# MurataBreakout_rev2.net
KiCad netlist of a schematic drawn in EAGLE
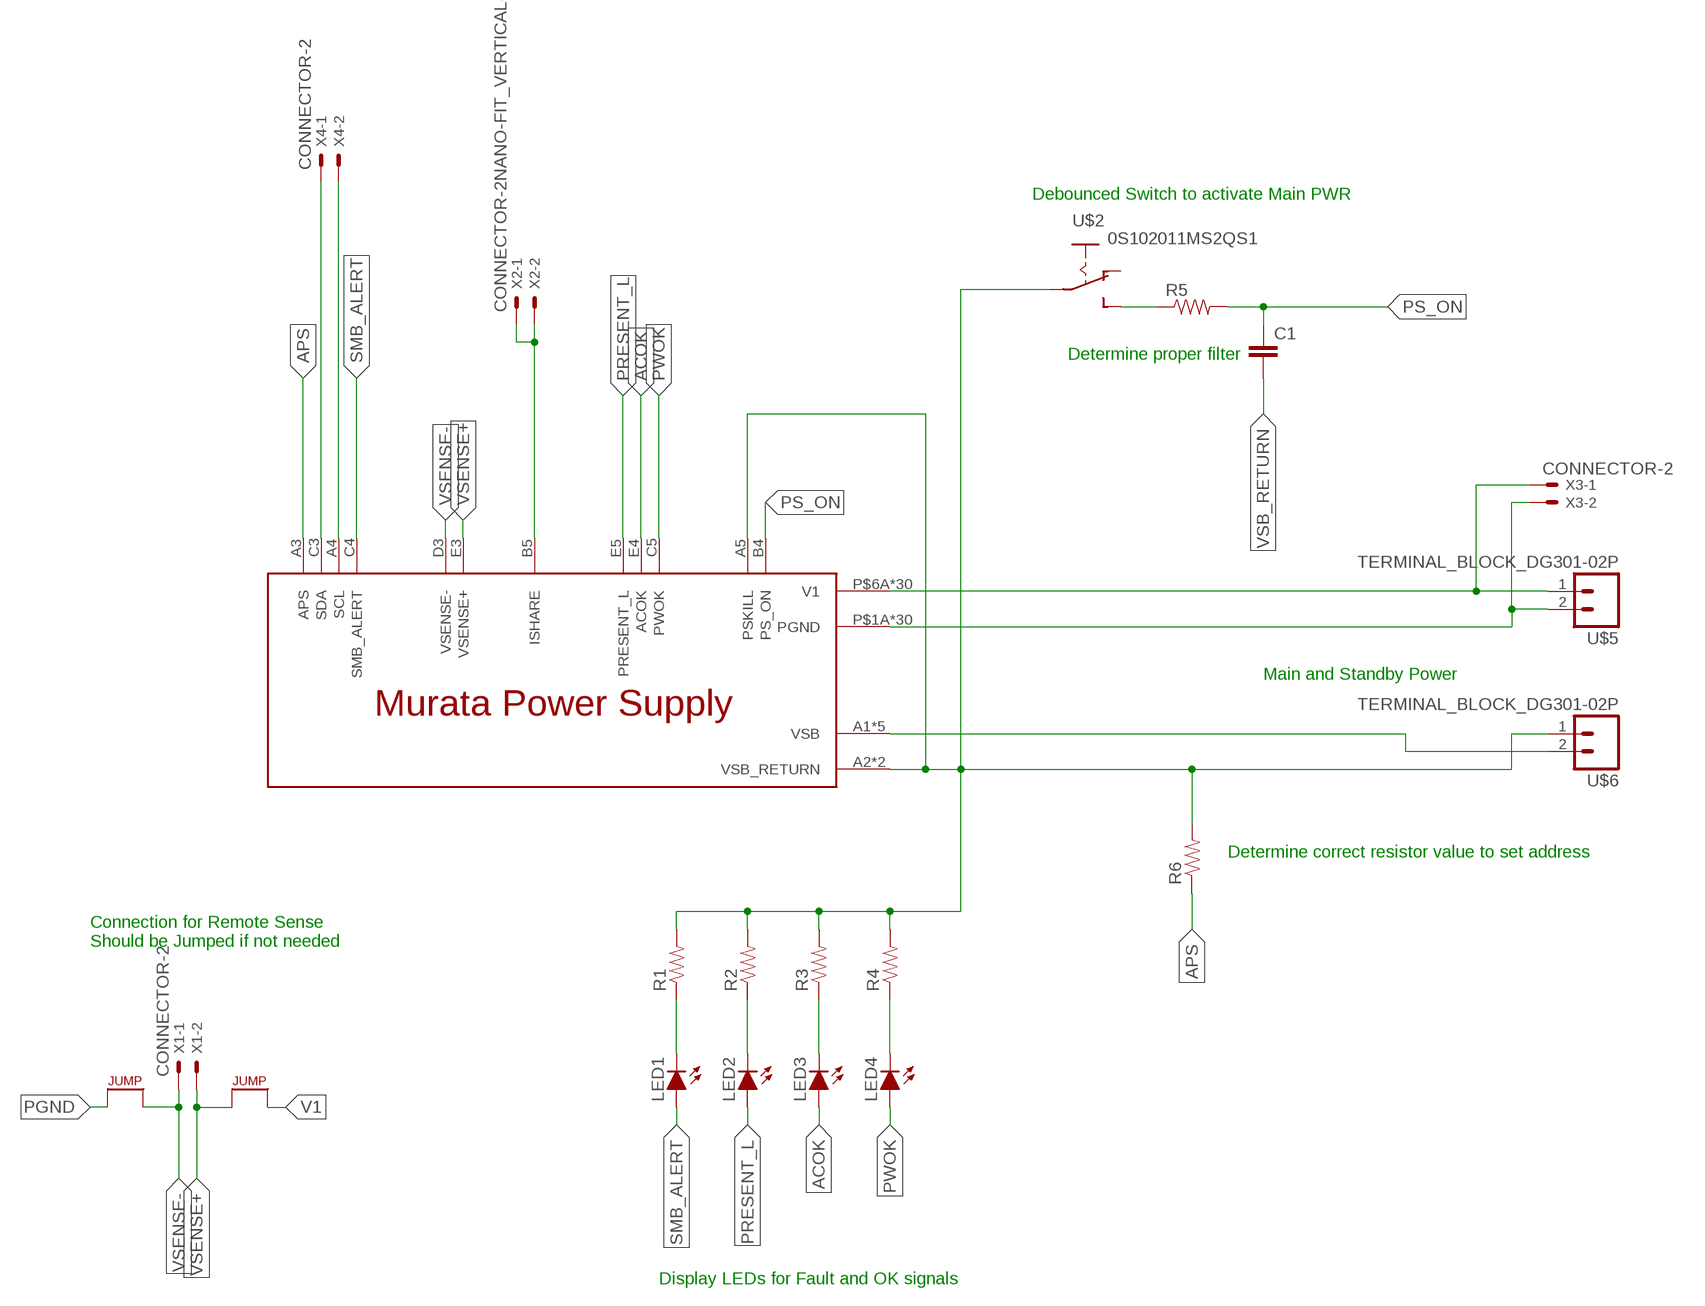
[diagram p0: schematic, sheet 1]

(export (version "E")
  (design (tool "Eeschema 10.0.6"))
  (components
    (comp (ref "C1")
      (value "CAP0805")
      (footprint "eagle-import:0805")
      (libsource (lib "eagle-import") (part "CAP0805"))
    )
    (comp (ref "LED1")
      (value "LED-0805")
      (footprint "eagle-import:LED-805")
      (libsource (lib "eagle-import") (part "LED-0805"))
    )
    (comp (ref "LED2")
      (value "LED-0805")
      (footprint "eagle-import:LED-805")
      (libsource (lib "eagle-import") (part "LED-0805"))
    )
    (comp (ref "LED3")
      (value "LED-0805")
      (footprint "eagle-import:LED-805")
      (libsource (lib "eagle-import") (part "LED-0805"))
    )
    (comp (ref "LED4")
      (value "LED-0805")
      (footprint "eagle-import:LED-805")
      (libsource (lib "eagle-import") (part "LED-0805"))
    )
    (comp (ref "R1")
      (value "RESISTOR0805-RES")
      (footprint "eagle-import:0805")
      (libsource (lib "eagle-import") (part "RESISTOR0805-RES"))
    )
    (comp (ref "R2")
      (value "RESISTOR0805-RES")
      (footprint "eagle-import:0805")
      (libsource (lib "eagle-import") (part "RESISTOR0805-RES"))
    )
    (comp (ref "R3")
      (value "RESISTOR0805-RES")
      (footprint "eagle-import:0805")
      (libsource (lib "eagle-import") (part "RESISTOR0805-RES"))
    )
    (comp (ref "R4")
      (value "RESISTOR0805-RES")
      (footprint "eagle-import:0805")
      (libsource (lib "eagle-import") (part "RESISTOR0805-RES"))
    )
    (comp (ref "R5")
      (value "RESISTOR0805-RES")
      (footprint "eagle-import:0805")
      (libsource (lib "eagle-import") (part "RESISTOR0805-RES"))
    )
    (comp (ref "R6")
      (value "RESISTOR0805-RES")
      (footprint "eagle-import:0805")
      (libsource (lib "eagle-import") (part "RESISTOR0805-RES"))
    )
    (comp (ref "U$1")
      (value "MURATA_POWER_SUPPLY")
      (footprint "eagle-import:MURATA_POWER_SUPPLY_CONNECTOR")
      (libsource (lib "eagle-import") (part "MURATA_POWER_SUPPLY"))
    )
    (comp (ref "U$2")
      (value "0S102011MS2QS1")
      (footprint "eagle-import:0S102011MS2QS1")
      (libsource (lib "eagle-import") (part "0S102011MS2QS1"))
    )
    (comp (ref "U$3")
      (value "JUMPER.1")
      (footprint "eagle-import:1X02")
      (libsource (lib "eagle-import") (part "JUMPER.1"))
    )
    (comp (ref "U$4")
      (value "JUMPER.1")
      (footprint "eagle-import:1X02")
      (libsource (lib "eagle-import") (part "JUMPER.1"))
    )
    (comp (ref "U$5")
      (value "TERMINAL_BLOCK_DG301-02P")
      (footprint "eagle-import:DG301-02P")
      (libsource (lib "eagle-import") (part "TERMINAL_BLOCK_DG301-02P"))
    )
    (comp (ref "U$6")
      (value "TERMINAL_BLOCK_DG301-02P")
      (footprint "eagle-import:DG301-02P")
      (libsource (lib "eagle-import") (part "TERMINAL_BLOCK_DG301-02P"))
    )
    (comp (ref "X1")
      (value "CONNECTOR-2")
      (footprint "eagle-import:MINIFIT_5566-2")
      (libsource (lib "eagle-import") (part "CONNECTOR-2"))
    )
    (comp (ref "X2")
      (value "CONNECTOR-2NANO-FIT_VERTICAL-2")
      (footprint "eagle-import:NANO-FIT_VERTICAL-2")
      (libsource (lib "eagle-import") (part "CONNECTOR-2NANO-FIT_VERTICAL-2"))
    )
    (comp (ref "X3")
      (value "CONNECTOR-2")
      (footprint "eagle-import:MINIFIT_5566-2")
      (libsource (lib "eagle-import") (part "CONNECTOR-2"))
    )
    (comp (ref "X4")
      (value "CONNECTOR-2")
      (footprint "eagle-import:MINIFIT_5566-2")
      (libsource (lib "eagle-import") (part "CONNECTOR-2"))
    )
  )
  (nets
    (net (code "1") (name "ACOK") (class "Default")
      (node (ref "LED3") (pin "A") (pinfunction "A_A") (pintype "passive"))
      (node (ref "U$1") (pin "E4") (pinfunction "ACOK_E4") (pintype "bidirectional"))
    )
    (net (code "2") (name "APS") (class "Default")
      (node (ref "R6") (pin "1") (pinfunction "1_1") (pintype "passive"))
      (node (ref "U$1") (pin "A3") (pinfunction "APS_A3") (pintype "bidirectional"))
    )
    (net (code "3") (name "Net-(LED1-PadC)") (class "Default")
      (node (ref "LED1") (pin "C") (pinfunction "C_C") (pintype "passive"))
      (node (ref "R1") (pin "1") (pinfunction "1_1") (pintype "passive"))
    )
    (net (code "4") (name "Net-(LED2-PadC)") (class "Default")
      (node (ref "LED2") (pin "C") (pinfunction "C_C") (pintype "passive"))
      (node (ref "R2") (pin "1") (pinfunction "1_1") (pintype "passive"))
    )
    (net (code "5") (name "Net-(LED3-PadC)") (class "Default")
      (node (ref "LED3") (pin "C") (pinfunction "C_C") (pintype "passive"))
      (node (ref "R3") (pin "1") (pinfunction "1_1") (pintype "passive"))
    )
    (net (code "6") (name "Net-(LED4-PadC)") (class "Default")
      (node (ref "LED4") (pin "C") (pinfunction "C_C") (pintype "passive"))
      (node (ref "R4") (pin "1") (pinfunction "1_1") (pintype "passive"))
    )
    (net (code "7") (name "Net-(U$1-ISHARE)") (class "Default")
      (node (ref "U$1") (pin "B5") (pinfunction "ISHARE_B5") (pintype "bidirectional"))
      (node (ref "X2") (pin "P$1") (pinfunction "S_P$1") (pintype "passive"))
      (node (ref "X2") (pin "P$2") (pinfunction "S_P$2") (pintype "passive"))
    )
    (net (code "8") (name "Net-(U$1-SCL)") (class "Default")
      (node (ref "U$1") (pin "A4") (pinfunction "SCL_A4") (pintype "bidirectional"))
      (node (ref "X4") (pin "2") (pinfunction "S_2") (pintype "passive"))
    )
    (net (code "9") (name "Net-(U$1-SDA)") (class "Default")
      (node (ref "U$1") (pin "C3") (pinfunction "SDA_C3") (pintype "bidirectional"))
      (node (ref "X4") (pin "1") (pinfunction "S_1") (pintype "passive"))
    )
    (net (code "10") (name "Net-(U$1-VSB-PadA1)") (class "Default")
      (node (ref "U$1") (pin "A1") (pinfunction "VSB_A1") (pintype "bidirectional"))
      (node (ref "U$1") (pin "B1") (pinfunction "VSB_B1") (pintype "bidirectional"))
      (node (ref "U$1") (pin "C1") (pinfunction "VSB_C1") (pintype "bidirectional"))
      (node (ref "U$1") (pin "D1") (pinfunction "VSB_D1") (pintype "bidirectional"))
      (node (ref "U$1") (pin "E1") (pinfunction "VSB_E1") (pintype "bidirectional"))
      (node (ref "U$6") (pin "2") (pinfunction "2_2") (pintype "passive"))
    )
    (net (code "11") (name "Net-(U$2-S)") (class "Default")
      (node (ref "R5") (pin "1") (pinfunction "1_1") (pintype "passive"))
      (node (ref "U$2") (pin "P$3") (pinfunction "S_P$3") (pintype "passive"))
    )
    (net (code "12") (name "PGND") (class "Default")
      (node (ref "U$1") (pin "P$1A") (pinfunction "PGND_P$1A") (pintype "bidirectional"))
      (node (ref "U$1") (pin "P$1B") (pinfunction "PGND_P$1B") (pintype "bidirectional"))
      (node (ref "U$1") (pin "P$1C") (pinfunction "PGND_P$1C") (pintype "bidirectional"))
      (node (ref "U$1") (pin "P$1D") (pinfunction "PGND_P$1D") (pintype "bidirectional"))
      (node (ref "U$1") (pin "P$1E") (pinfunction "PGND_P$1E") (pintype "bidirectional"))
      (node (ref "U$1") (pin "P$1F") (pinfunction "PGND_P$1F") (pintype "bidirectional"))
      (node (ref "U$1") (pin "P$2A") (pinfunction "PGND_P$2A") (pintype "bidirectional"))
      (node (ref "U$1") (pin "P$2B") (pinfunction "PGND_P$2B") (pintype "bidirectional"))
      (node (ref "U$1") (pin "P$2C") (pinfunction "PGND_P$2C") (pintype "bidirectional"))
      (node (ref "U$1") (pin "P$2D") (pinfunction "PGND_P$2D") (pintype "bidirectional"))
      (node (ref "U$1") (pin "P$2E") (pinfunction "PGND_P$2E") (pintype "bidirectional"))
      (node (ref "U$1") (pin "P$2F") (pinfunction "PGND_P$2F") (pintype "bidirectional"))
      (node (ref "U$1") (pin "P$3A") (pinfunction "PGND_P$3A") (pintype "bidirectional"))
      (node (ref "U$1") (pin "P$3B") (pinfunction "PGND_P$3B") (pintype "bidirectional"))
      (node (ref "U$1") (pin "P$3C") (pinfunction "PGND_P$3C") (pintype "bidirectional"))
      (node (ref "U$1") (pin "P$3D") (pinfunction "PGND_P$3D") (pintype "bidirectional"))
      (node (ref "U$1") (pin "P$3E") (pinfunction "PGND_P$3E") (pintype "bidirectional"))
      (node (ref "U$1") (pin "P$3F") (pinfunction "PGND_P$3F") (pintype "bidirectional"))
      (node (ref "U$1") (pin "P$4A") (pinfunction "PGND_P$4A") (pintype "bidirectional"))
      (node (ref "U$1") (pin "P$4B") (pinfunction "PGND_P$4B") (pintype "bidirectional"))
      (node (ref "U$1") (pin "P$4C") (pinfunction "PGND_P$4C") (pintype "bidirectional"))
      (node (ref "U$1") (pin "P$4D") (pinfunction "PGND_P$4D") (pintype "bidirectional"))
      (node (ref "U$1") (pin "P$4E") (pinfunction "PGND_P$4E") (pintype "bidirectional"))
      (node (ref "U$1") (pin "P$4F") (pinfunction "PGND_P$4F") (pintype "bidirectional"))
      (node (ref "U$1") (pin "P$5A") (pinfunction "PGND_P$5A") (pintype "bidirectional"))
      (node (ref "U$1") (pin "P$5B") (pinfunction "PGND_P$5B") (pintype "bidirectional"))
      (node (ref "U$1") (pin "P$5C") (pinfunction "PGND_P$5C") (pintype "bidirectional"))
      (node (ref "U$1") (pin "P$5D") (pinfunction "PGND_P$5D") (pintype "bidirectional"))
      (node (ref "U$1") (pin "P$5E") (pinfunction "PGND_P$5E") (pintype "bidirectional"))
      (node (ref "U$1") (pin "P$5F") (pinfunction "PGND_P$5F") (pintype "bidirectional"))
      (node (ref "U$4") (pin "1") (pinfunction "P$1_1") (pintype "bidirectional"))
      (node (ref "U$5") (pin "2") (pinfunction "2_2") (pintype "passive"))
      (node (ref "X3") (pin "2") (pinfunction "S_2") (pintype "passive"))
    )
    (net (code "13") (name "PRESENT_L") (class "Default")
      (node (ref "LED2") (pin "A") (pinfunction "A_A") (pintype "passive"))
      (node (ref "U$1") (pin "E5") (pinfunction "PRESENT_L_E5") (pintype "bidirectional"))
    )
    (net (code "14") (name "PS_ON") (class "Default")
      (node (ref "C1") (pin "1") (pinfunction "1_1") (pintype "passive"))
      (node (ref "R5") (pin "2") (pinfunction "2_2") (pintype "passive"))
      (node (ref "U$1") (pin "B4") (pinfunction "PS_ON_B4") (pintype "bidirectional"))
    )
    (net (code "15") (name "PWOK") (class "Default")
      (node (ref "LED4") (pin "A") (pinfunction "A_A") (pintype "passive"))
      (node (ref "U$1") (pin "C5") (pinfunction "PWOK_C5") (pintype "bidirectional"))
    )
    (net (code "16") (name "SMB_ALERT") (class "Default")
      (node (ref "LED1") (pin "A") (pinfunction "A_A") (pintype "passive"))
      (node (ref "U$1") (pin "C4") (pinfunction "SMB_ALERT_C4") (pintype "bidirectional"))
    )
    (net (code "17") (name "V1") (class "Default")
      (node (ref "U$1") (pin "P$10A") (pinfunction "V1_P$10A") (pintype "bidirectional"))
      (node (ref "U$1") (pin "P$10B") (pinfunction "V1_P$10B") (pintype "bidirectional"))
      (node (ref "U$1") (pin "P$10C") (pinfunction "V1_P$10C") (pintype "bidirectional"))
      (node (ref "U$1") (pin "P$10D") (pinfunction "V1_P$10D") (pintype "bidirectional"))
      (node (ref "U$1") (pin "P$10E") (pinfunction "V1_P$10E") (pintype "bidirectional"))
      (node (ref "U$1") (pin "P$10F") (pinfunction "V1_P$10F") (pintype "bidirectional"))
      (node (ref "U$1") (pin "P$6A") (pinfunction "V1_P$6A") (pintype "bidirectional"))
      (node (ref "U$1") (pin "P$6B") (pinfunction "V1_P$6B") (pintype "bidirectional"))
      (node (ref "U$1") (pin "P$6C") (pinfunction "V1_P$6C") (pintype "bidirectional"))
      (node (ref "U$1") (pin "P$6D") (pinfunction "V1_P$6D") (pintype "bidirectional"))
      (node (ref "U$1") (pin "P$6E") (pinfunction "V1_P$6E") (pintype "bidirectional"))
      (node (ref "U$1") (pin "P$6F") (pinfunction "V1_P$6F") (pintype "bidirectional"))
      (node (ref "U$1") (pin "P$7A") (pinfunction "V1_P$7A") (pintype "bidirectional"))
      (node (ref "U$1") (pin "P$7B") (pinfunction "V1_P$7B") (pintype "bidirectional"))
      (node (ref "U$1") (pin "P$7C") (pinfunction "V1_P$7C") (pintype "bidirectional"))
      (node (ref "U$1") (pin "P$7D") (pinfunction "V1_P$7D") (pintype "bidirectional"))
      (node (ref "U$1") (pin "P$7E") (pinfunction "V1_P$7E") (pintype "bidirectional"))
      (node (ref "U$1") (pin "P$7F") (pinfunction "V1_P$7F") (pintype "bidirectional"))
      (node (ref "U$1") (pin "P$8A") (pinfunction "V1_P$8A") (pintype "bidirectional"))
      (node (ref "U$1") (pin "P$8B") (pinfunction "V1_P$8B") (pintype "bidirectional"))
      (node (ref "U$1") (pin "P$8C") (pinfunction "V1_P$8C") (pintype "bidirectional"))
      (node (ref "U$1") (pin "P$8D") (pinfunction "V1_P$8D") (pintype "bidirectional"))
      (node (ref "U$1") (pin "P$8E") (pinfunction "V1_P$8E") (pintype "bidirectional"))
      (node (ref "U$1") (pin "P$8F") (pinfunction "V1_P$8F") (pintype "bidirectional"))
      (node (ref "U$1") (pin "P$9A") (pinfunction "V1_P$9A") (pintype "bidirectional"))
      (node (ref "U$1") (pin "P$9B") (pinfunction "V1_P$9B") (pintype "bidirectional"))
      (node (ref "U$1") (pin "P$9C") (pinfunction "V1_P$9C") (pintype "bidirectional"))
      (node (ref "U$1") (pin "P$9D") (pinfunction "V1_P$9D") (pintype "bidirectional"))
      (node (ref "U$1") (pin "P$9E") (pinfunction "V1_P$9E") (pintype "bidirectional"))
      (node (ref "U$1") (pin "P$9F") (pinfunction "V1_P$9F") (pintype "bidirectional"))
      (node (ref "U$3") (pin "2") (pinfunction "P$2_2") (pintype "bidirectional"))
      (node (ref "U$5") (pin "1") (pinfunction "1_1") (pintype "passive"))
      (node (ref "X3") (pin "1") (pinfunction "S_1") (pintype "passive"))
    )
    (net (code "18") (name "VSB_RETURN") (class "Default")
      (node (ref "C1") (pin "2") (pinfunction "2_2") (pintype "passive"))
      (node (ref "R1") (pin "2") (pinfunction "2_2") (pintype "passive"))
      (node (ref "R2") (pin "2") (pinfunction "2_2") (pintype "passive"))
      (node (ref "R3") (pin "2") (pinfunction "2_2") (pintype "passive"))
      (node (ref "R4") (pin "2") (pinfunction "2_2") (pintype "passive"))
      (node (ref "R6") (pin "2") (pinfunction "2_2") (pintype "passive"))
      (node (ref "U$1") (pin "A2") (pinfunction "VSB_RETURN_A2") (pintype "bidirectional"))
      (node (ref "U$1") (pin "A5") (pinfunction "PSKILL_A5") (pintype "bidirectional"))
      (node (ref "U$1") (pin "B2") (pinfunction "VSB_RETURN_B2") (pintype "bidirectional"))
      (node (ref "U$2") (pin "P$2") (pinfunction "P_P$2") (pintype "passive"))
      (node (ref "U$6") (pin "1") (pinfunction "1_1") (pintype "passive"))
    )
    (net (code "19") (name "VSENSE+") (class "Default")
      (node (ref "U$1") (pin "E3") (pinfunction "VSENSE+_E3") (pintype "bidirectional"))
      (node (ref "U$3") (pin "1") (pinfunction "P$1_1") (pintype "bidirectional"))
      (node (ref "X1") (pin "2") (pinfunction "S_2") (pintype "passive"))
    )
    (net (code "20") (name "VSENSE-") (class "Default")
      (node (ref "U$1") (pin "D3") (pinfunction "VSENSE-_D3") (pintype "bidirectional"))
      (node (ref "U$4") (pin "2") (pinfunction "P$2_2") (pintype "bidirectional"))
      (node (ref "X1") (pin "1") (pinfunction "S_1") (pintype "passive"))
    )
    (net (code "21") (name "unconnected-(U$2-O-PadP$1)") (class "Default")
      (node (ref "U$2") (pin "P$1") (pinfunction "O_P$1") (pintype "passive"))
    )
  )
)
